# AmpliTR.net
KiCad netlist of a schematic drawn in EAGLE
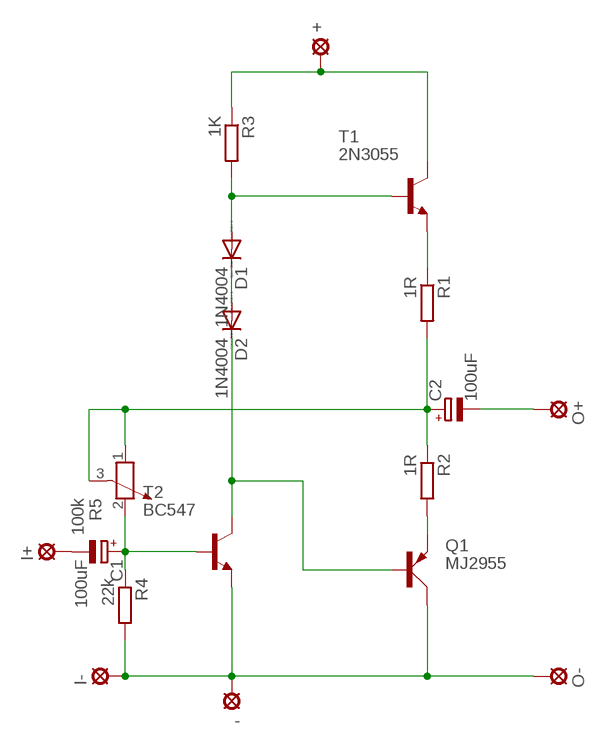
[diagram p0: schematic, sheet 1]

(export (version "E")
  (design (tool "Eeschema 10.0.6"))
  (components
    (comp (ref "+")
      (value "LSP10")
      (footprint "eagle-import:LSP10")
      (libsource (lib "eagle-import") (part "LSP10"))
    )
    (comp (ref "-")
      (value "LSP10")
      (footprint "eagle-import:LSP10")
      (libsource (lib "eagle-import") (part "LSP10"))
    )
    (comp (ref "C1")
      (value "100uF")
      (footprint "eagle-import:E2-5")
      (libsource (lib "eagle-import") (part "CPOL-EUE2-5"))
    )
    (comp (ref "C2")
      (value "100uF")
      (footprint "eagle-import:E2-5")
      (libsource (lib "eagle-import") (part "CPOL-EUE2-5"))
    )
    (comp (ref "D1")
      (value "1N4004")
      (footprint "eagle-import:DO41-10")
      (libsource (lib "eagle-import") (part "1N4004"))
    )
    (comp (ref "D2")
      (value "1N4004")
      (footprint "eagle-import:DO41-10")
      (libsource (lib "eagle-import") (part "1N4004"))
    )
    (comp (ref "I+")
      (value "LSP10")
      (footprint "eagle-import:LSP10")
      (libsource (lib "eagle-import") (part "LSP10"))
    )
    (comp (ref "I-")
      (value "LSP10")
      (footprint "eagle-import:LSP10")
      (libsource (lib "eagle-import") (part "LSP10"))
    )
    (comp (ref "O+")
      (value "LSP10")
      (footprint "eagle-import:LSP10")
      (libsource (lib "eagle-import") (part "LSP10"))
    )
    (comp (ref "O-")
      (value "LSP10")
      (footprint "eagle-import:LSP10")
      (libsource (lib "eagle-import") (part "LSP10"))
    )
    (comp (ref "Q1")
      (value "MJ2955")
      (footprint "eagle-import:TO3A")
      (libsource (lib "eagle-import") (part "MJ2955"))
    )
    (comp (ref "R1")
      (value "1R")
      (footprint "eagle-import:0414V")
      (libsource (lib "eagle-import") (part "R-EU_0414/5V"))
    )
    (comp (ref "R2")
      (value "1R")
      (footprint "eagle-import:0414V")
      (libsource (lib "eagle-import") (part "R-EU_0414/5V"))
    )
    (comp (ref "R3")
      (value "1K")
      (footprint "eagle-import:0414V")
      (libsource (lib "eagle-import") (part "R-EU_0414/5V"))
    )
    (comp (ref "R4")
      (value "22k")
      (footprint "eagle-import:0414V")
      (libsource (lib "eagle-import") (part "R-EU_0414/5V"))
    )
    (comp (ref "R5")
      (value "100k")
      (footprint "eagle-import:PT-10S")
      (libsource (lib "eagle-import") (part "POTENTIOMETER_PT-10S"))
    )
    (comp (ref "T1")
      (value "2N3055")
      (footprint "eagle-import:TO3")
      (libsource (lib "eagle-import") (part "2N3055"))
    )
    (comp (ref "T2")
      (value "BC547")
      (footprint "eagle-import:TO92")
      (libsource (lib "eagle-import") (part "BC547"))
    )
  )
  (nets
    (net (code "1") (name "Net-(+-PadMP)") (class "Default")
      (node (ref "+") (pin "MP") (pinfunction "MP_MP") (pintype "passive"))
      (node (ref "R3") (pin "1") (pinfunction "1_1") (pintype "passive"))
      (node (ref "T1") (pin "C") (pinfunction "C_C") (pintype "passive"))
      (node (ref "T1") (pin "C/") (pinfunction "C_C/") (pintype "passive"))
    )
    (net (code "2") (name "Net-(C1-Pad-)") (class "Default")
      (node (ref "C1") (pin "-") (pinfunction "-_-") (pintype "passive"))
      (node (ref "I+") (pin "MP") (pinfunction "MP_MP") (pintype "passive"))
    )
    (net (code "3") (name "Net-(C2-Pad+)") (class "Default")
      (node (ref "C2") (pin "+") (pinfunction "+_+") (pintype "passive"))
      (node (ref "R1") (pin "2") (pinfunction "2_2") (pintype "passive"))
      (node (ref "R2") (pin "1") (pinfunction "1_1") (pintype "passive"))
      (node (ref "R5") (pin "1") (pinfunction "1_1") (pintype "passive"))
      (node (ref "R5") (pin "3") (pinfunction "3_3") (pintype "passive"))
    )
    (net (code "4") (name "Net-(C2-Pad-)") (class "Default")
      (node (ref "C2") (pin "-") (pinfunction "-_-") (pintype "passive"))
      (node (ref "O+") (pin "MP") (pinfunction "MP_MP") (pintype "passive"))
    )
    (net (code "5") (name "Net-(D1-PadA)") (class "Default")
      (node (ref "D1") (pin "A") (pinfunction "A_A") (pintype "passive"))
      (node (ref "R3") (pin "2") (pinfunction "2_2") (pintype "passive"))
      (node (ref "T1") (pin "B") (pinfunction "B_B") (pintype "passive"))
    )
    (net (code "6") (name "Net-(D1-PadC)") (class "Default")
      (node (ref "D1") (pin "C") (pinfunction "C_C") (pintype "passive"))
      (node (ref "D2") (pin "A") (pinfunction "A_A") (pintype "passive"))
    )
    (net (code "7") (name "Net-(Q1-PadE)") (class "Default")
      (node (ref "Q1") (pin "E") (pinfunction "E_E") (pintype "passive"))
      (node (ref "R2") (pin "2") (pinfunction "2_2") (pintype "passive"))
    )
    (net (code "8") (name "Net-(R1-Pad1)") (class "Default")
      (node (ref "R1") (pin "1") (pinfunction "1_1") (pintype "passive"))
      (node (ref "T1") (pin "E") (pinfunction "E_E") (pintype "passive"))
    )
    (net (code "9") (name "Net-(T2-B)") (class "Default")
      (node (ref "C1") (pin "+") (pinfunction "+_+") (pintype "passive"))
      (node (ref "R4") (pin "1") (pinfunction "1_1") (pintype "passive"))
      (node (ref "R5") (pin "2") (pinfunction "2_2") (pintype "passive"))
      (node (ref "T2") (pin "2") (pinfunction "B_2") (pintype "passive"))
    )
    (net (code "10") (name "Net-(T2-C)") (class "Default")
      (node (ref "D2") (pin "C") (pinfunction "C_C") (pintype "passive"))
      (node (ref "Q1") (pin "B") (pinfunction "B_B") (pintype "passive"))
      (node (ref "T2") (pin "3") (pinfunction "C_3") (pintype "passive"))
    )
    (net (code "11") (name "Net-(T2-E)") (class "Default")
      (node (ref "-") (pin "MP") (pinfunction "MP_MP") (pintype "passive"))
      (node (ref "I-") (pin "MP") (pinfunction "MP_MP") (pintype "passive"))
      (node (ref "O-") (pin "MP") (pinfunction "MP_MP") (pintype "passive"))
      (node (ref "Q1") (pin "C") (pinfunction "C_C") (pintype "passive"))
      (node (ref "Q1") (pin "C1") (pinfunction "C_C1") (pintype "passive"))
      (node (ref "R4") (pin "2") (pinfunction "2_2") (pintype "passive"))
      (node (ref "T2") (pin "1") (pinfunction "E_1") (pintype "passive"))
    )
  )
)
